# Basic-Computer.net
KiCad netlist of a schematic drawn in EAGLE
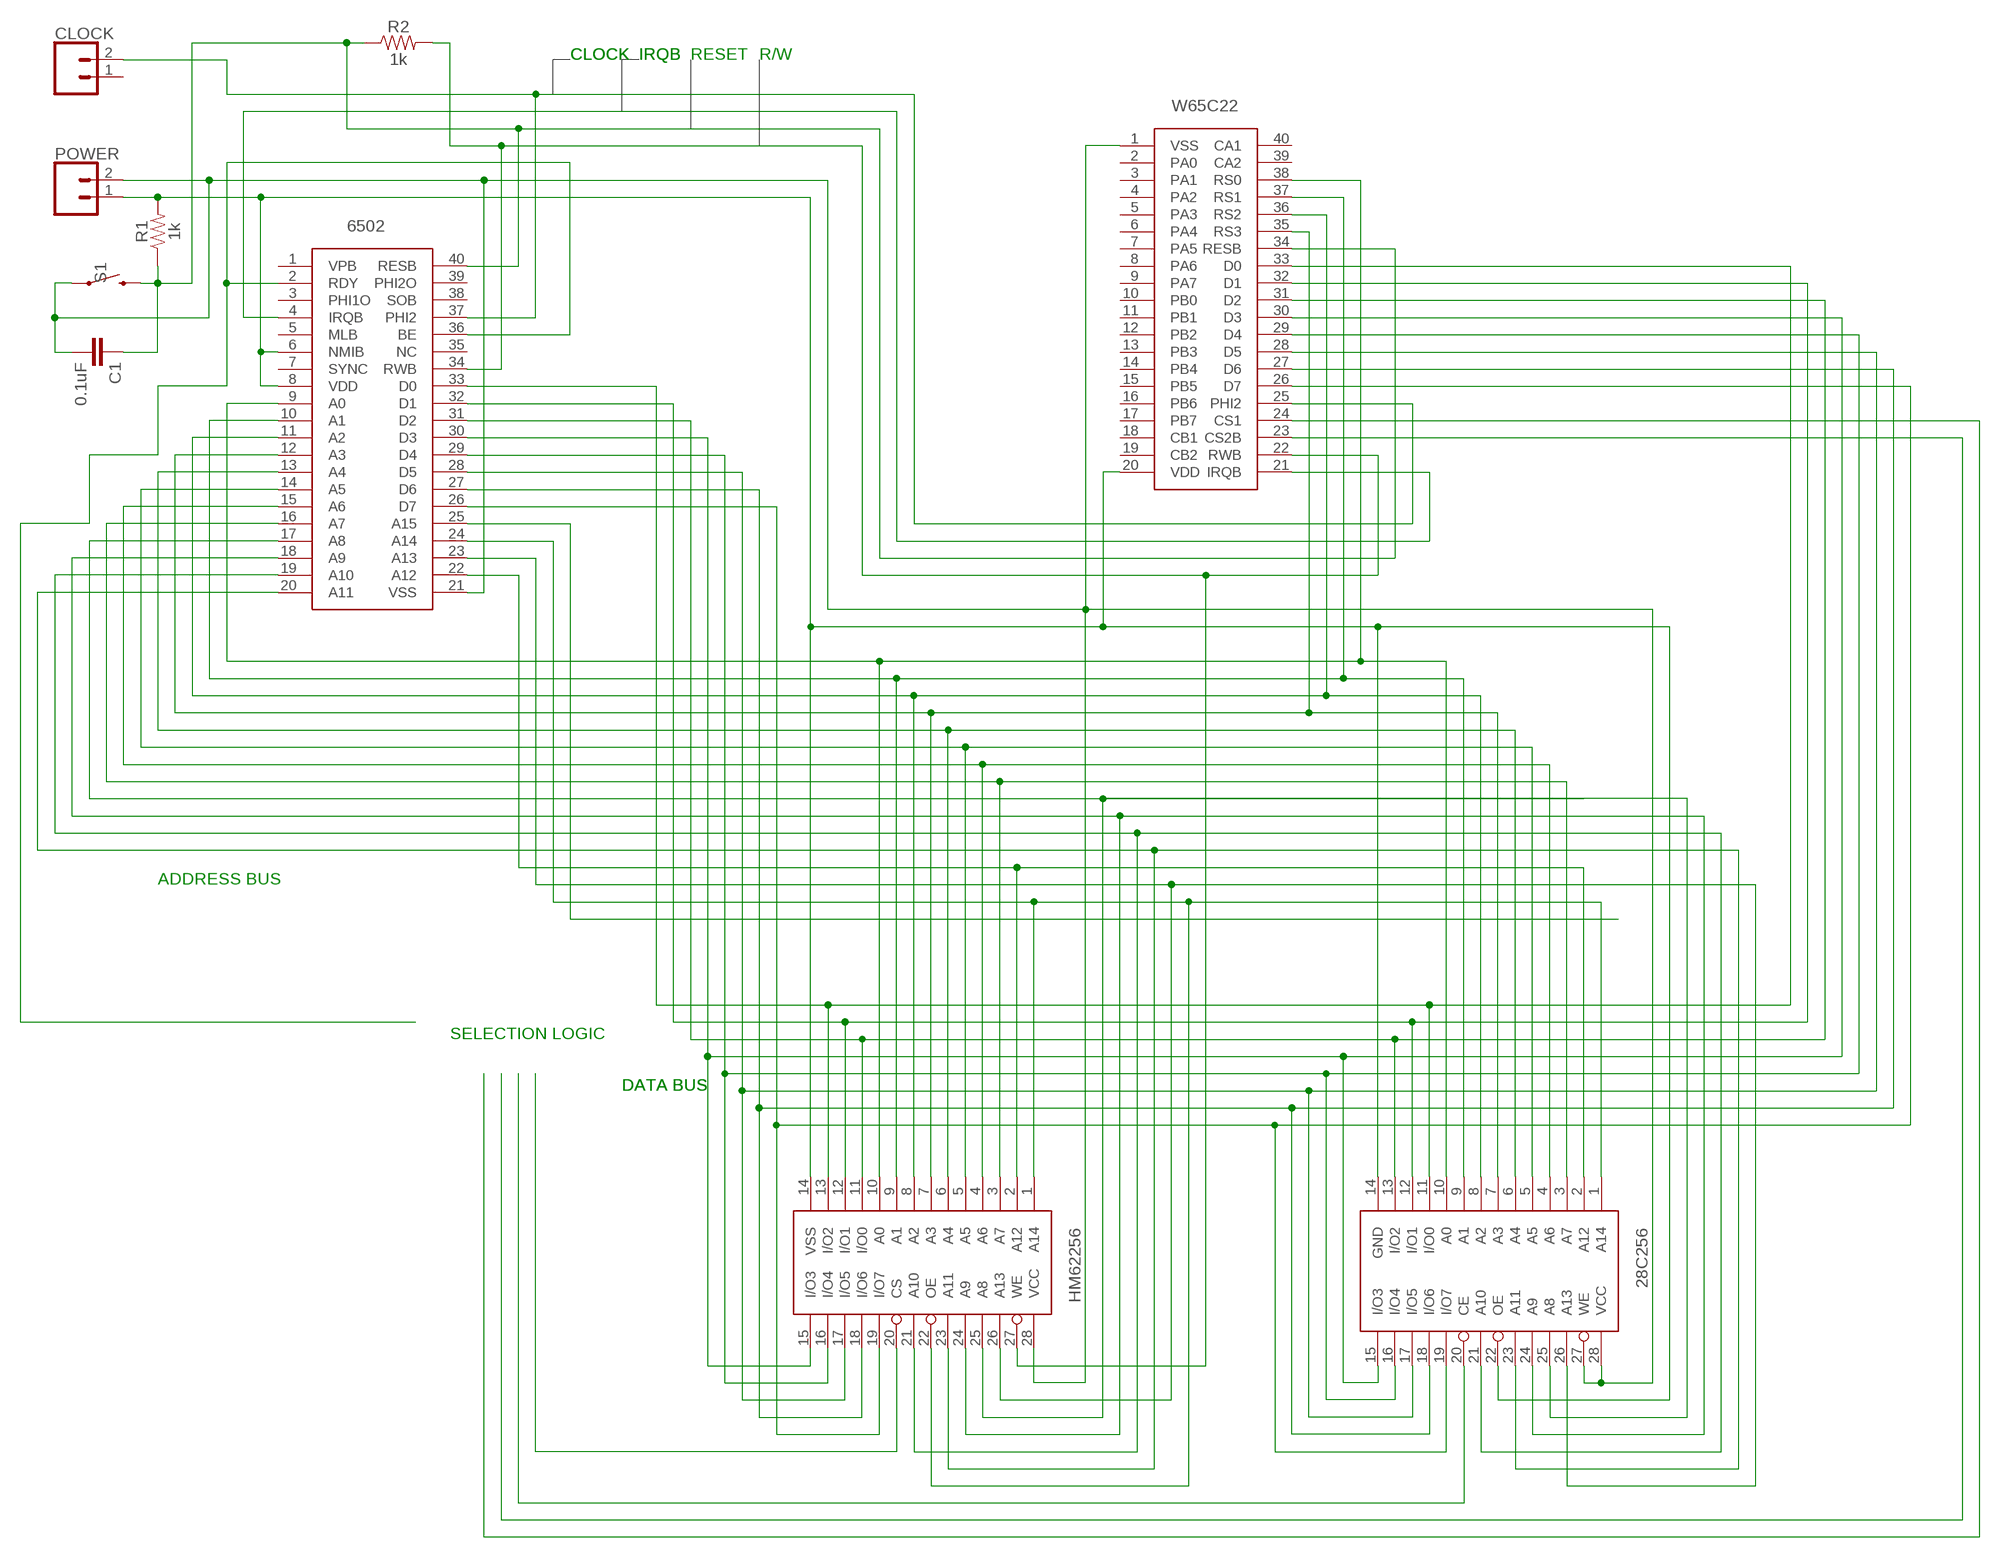
[diagram p0: schematic, sheet 1]

(export (version "E")
  (design (tool "Eeschema 10.0.6"))
  (components
    (comp (ref "C1")
      (value "0.1uF")
      (footprint "eagle-import:0402")
      (libsource (lib "eagle-import") (part "0.1UF-0402-16V-10%"))
    )
    (comp (ref "CLOCK")
      (value "CONN_02POGO_PIN_HOLES_ONLY")
      (footprint "eagle-import:1X02_PP_HOLES_ONLY")
      (libsource (lib "eagle-import") (part "CONN_02POGO_PIN_HOLES_ONLY"))
    )
    (comp (ref "POWER")
      (value "CONN_02POGO_PIN_HOLES_ONLY")
      (footprint "eagle-import:1X02_PP_HOLES_ONLY")
      (libsource (lib "eagle-import") (part "CONN_02POGO_PIN_HOLES_ONLY"))
    )
    (comp (ref "R1")
      (value "1k")
      (footprint "eagle-import:AXIAL-0.3")
      (libsource (lib "eagle-import") (part "1KOHM-HORIZ-1/4W-5%"))
    )
    (comp (ref "R2")
      (value "1k")
      (footprint "eagle-import:AXIAL-0.3")
      (libsource (lib "eagle-import") (part "1KOHM-HORIZ-1/4W-5%"))
    )
    (comp (ref "S1")
      (value "MOMENTARY-SWITCH-SPST-PTH-6.0MM")
      (footprint "eagle-import:TACTILE_SWITCH_PTH_6.0MM")
      (libsource (lib "eagle-import") (part "MOMENTARY-SWITCH-SPST-PTH-6.0MM"))
    )
    (comp (ref "U$1")
      (value "C6502")
      (footprint "eagle-import:DIP1150W53P250L4975H200Q40B")
      (libsource (lib "eagle-import") (part "C6502"))
    )
    (comp (ref "U$2")
      (value "W65C22")
      (footprint "eagle-import:DIP1150W53P250L4975H200Q40B")
      (libsource (lib "eagle-import") (part "W65C22"))
    )
    (comp (ref "U$3")
      (value "28C256")
      (footprint "eagle-import:DIP1722W26P254L3450H508Q28B")
      (libsource (lib "eagle-import") (part "28C256"))
    )
    (comp (ref "U$4")
      (value "HM62256")
      (footprint "eagle-import:DIP1722W26P254L3450H508Q28B")
      (libsource (lib "eagle-import") (part "HM62256"))
    )
  )
  (nets
    (net (code "1") (name "Net-(R1-1)") (class "Default")
      (node (ref "C1") (pin "1") (pinfunction "1_1") (pintype "passive"))
      (node (ref "R1") (pin "P$1") (pinfunction "1_P$1") (pintype "passive"))
      (node (ref "R2") (pin "P$1") (pinfunction "1_P$1") (pintype "passive"))
      (node (ref "S1") (pin "3") (pinfunction "2_3") (pintype "passive"))
      (node (ref "U$1") (pin "40") (pinfunction "RESB_40") (pintype "bidirectional"))
      (node (ref "U$2") (pin "34") (pinfunction "RESB_34") (pintype "bidirectional"))
    )
    (net (code "2") (name "Net-(R1-2)") (class "Default")
      (node (ref "POWER") (pin "1") (pinfunction "1_1") (pintype "passive"))
      (node (ref "R1") (pin "P$2") (pinfunction "2_P$2") (pintype "passive"))
      (node (ref "U$1") (pin "6") (pinfunction "NMIB_6") (pintype "bidirectional"))
      (node (ref "U$1") (pin "8") (pinfunction "VDD_8") (pintype "bidirectional"))
      (node (ref "U$2") (pin "20") (pinfunction "VDD_20") (pintype "bidirectional"))
      (node (ref "U$3") (pin "14") (pinfunction "GND_14") (pintype "bidirectional"))
      (node (ref "U$3") (pin "22") (pinfunction "OE_22") (pintype "bidirectional"))
      (node (ref "U$4") (pin "14") (pinfunction "VSS_14") (pintype "bidirectional"))
    )
    (net (code "3") (name "Net-(R2-2)") (class "Default")
      (node (ref "R2") (pin "P$2") (pinfunction "2_P$2") (pintype "passive"))
      (node (ref "U$1") (pin "34") (pinfunction "RWB_34") (pintype "bidirectional"))
      (node (ref "U$2") (pin "22") (pinfunction "RWB_22") (pintype "bidirectional"))
      (node (ref "U$4") (pin "27") (pinfunction "WE_27") (pintype "bidirectional"))
    )
    (net (code "4") (name "Net-(U$1-A0)") (class "Default")
      (node (ref "U$1") (pin "9") (pinfunction "A0_9") (pintype "bidirectional"))
      (node (ref "U$2") (pin "38") (pinfunction "RS0_38") (pintype "bidirectional"))
      (node (ref "U$3") (pin "10") (pinfunction "A0_10") (pintype "bidirectional"))
      (node (ref "U$4") (pin "10") (pinfunction "A0_10") (pintype "bidirectional"))
    )
    (net (code "5") (name "Net-(U$1-A1)") (class "Default")
      (node (ref "U$1") (pin "10") (pinfunction "A1_10") (pintype "bidirectional"))
      (node (ref "U$2") (pin "37") (pinfunction "RS1_37") (pintype "bidirectional"))
      (node (ref "U$3") (pin "9") (pinfunction "A1_9") (pintype "bidirectional"))
      (node (ref "U$4") (pin "9") (pinfunction "A1_9") (pintype "bidirectional"))
    )
    (net (code "6") (name "Net-(U$1-A2)") (class "Default")
      (node (ref "U$1") (pin "11") (pinfunction "A2_11") (pintype "bidirectional"))
      (node (ref "U$2") (pin "36") (pinfunction "RS2_36") (pintype "bidirectional"))
      (node (ref "U$3") (pin "8") (pinfunction "A2_8") (pintype "bidirectional"))
      (node (ref "U$4") (pin "8") (pinfunction "A2_8") (pintype "bidirectional"))
    )
    (net (code "7") (name "Net-(U$1-A3)") (class "Default")
      (node (ref "U$1") (pin "12") (pinfunction "A3_12") (pintype "bidirectional"))
      (node (ref "U$2") (pin "35") (pinfunction "RS3_35") (pintype "bidirectional"))
      (node (ref "U$3") (pin "7") (pinfunction "A3_7") (pintype "bidirectional"))
      (node (ref "U$4") (pin "7") (pinfunction "A3_7") (pintype "bidirectional"))
    )
    (net (code "8") (name "Net-(U$1-A4)") (class "Default")
      (node (ref "U$1") (pin "13") (pinfunction "A4_13") (pintype "bidirectional"))
      (node (ref "U$3") (pin "6") (pinfunction "A4_6") (pintype "bidirectional"))
      (node (ref "U$4") (pin "6") (pinfunction "A4_6") (pintype "bidirectional"))
    )
    (net (code "9") (name "Net-(U$1-A5)") (class "Default")
      (node (ref "U$1") (pin "14") (pinfunction "A5_14") (pintype "bidirectional"))
      (node (ref "U$3") (pin "5") (pinfunction "A5_5") (pintype "bidirectional"))
      (node (ref "U$4") (pin "5") (pinfunction "A5_5") (pintype "bidirectional"))
    )
    (net (code "10") (name "Net-(U$1-A6)") (class "Default")
      (node (ref "U$1") (pin "15") (pinfunction "A6_15") (pintype "bidirectional"))
      (node (ref "U$3") (pin "4") (pinfunction "A6_4") (pintype "bidirectional"))
      (node (ref "U$4") (pin "4") (pinfunction "A6_4") (pintype "bidirectional"))
    )
    (net (code "11") (name "Net-(U$1-A7)") (class "Default")
      (node (ref "U$1") (pin "16") (pinfunction "A7_16") (pintype "bidirectional"))
      (node (ref "U$3") (pin "3") (pinfunction "A7_3") (pintype "bidirectional"))
      (node (ref "U$4") (pin "3") (pinfunction "A7_3") (pintype "bidirectional"))
    )
    (net (code "12") (name "Net-(U$1-A8)") (class "Default")
      (node (ref "U$1") (pin "17") (pinfunction "A8_17") (pintype "bidirectional"))
      (node (ref "U$3") (pin "25") (pinfunction "A8_25") (pintype "bidirectional"))
      (node (ref "U$4") (pin "25") (pinfunction "A8_25") (pintype "bidirectional"))
    )
    (net (code "13") (name "Net-(U$1-A9)") (class "Default")
      (node (ref "U$1") (pin "18") (pinfunction "A9_18") (pintype "bidirectional"))
      (node (ref "U$3") (pin "24") (pinfunction "A9_24") (pintype "bidirectional"))
      (node (ref "U$4") (pin "24") (pinfunction "A9_24") (pintype "bidirectional"))
    )
    (net (code "14") (name "Net-(U$1-A10)") (class "Default")
      (node (ref "U$1") (pin "19") (pinfunction "A10_19") (pintype "bidirectional"))
      (node (ref "U$3") (pin "21") (pinfunction "A10_21") (pintype "bidirectional"))
      (node (ref "U$4") (pin "21") (pinfunction "A10_21") (pintype "bidirectional"))
    )
    (net (code "15") (name "Net-(U$1-A11)") (class "Default")
      (node (ref "U$1") (pin "20") (pinfunction "A11_20") (pintype "bidirectional"))
      (node (ref "U$3") (pin "23") (pinfunction "A11_23") (pintype "bidirectional"))
      (node (ref "U$4") (pin "23") (pinfunction "A11_23") (pintype "bidirectional"))
    )
    (net (code "16") (name "Net-(U$1-A12)") (class "Default")
      (node (ref "U$1") (pin "22") (pinfunction "A12_22") (pintype "bidirectional"))
      (node (ref "U$3") (pin "2") (pinfunction "A12_2") (pintype "bidirectional"))
      (node (ref "U$4") (pin "2") (pinfunction "A12_2") (pintype "bidirectional"))
    )
    (net (code "17") (name "Net-(U$1-A13)") (class "Default")
      (node (ref "U$1") (pin "23") (pinfunction "A13_23") (pintype "bidirectional"))
      (node (ref "U$3") (pin "26") (pinfunction "A13_26") (pintype "bidirectional"))
      (node (ref "U$4") (pin "26") (pinfunction "A13_26") (pintype "bidirectional"))
    )
    (net (code "18") (name "Net-(U$1-A14)") (class "Default")
      (node (ref "U$1") (pin "24") (pinfunction "A14_24") (pintype "bidirectional"))
      (node (ref "U$3") (pin "1") (pinfunction "A14_1") (pintype "bidirectional"))
      (node (ref "U$4") (pin "1") (pinfunction "A14_1") (pintype "bidirectional"))
      (node (ref "U$4") (pin "22") (pinfunction "OE_22") (pintype "bidirectional"))
    )
    (net (code "19") (name "Net-(U$1-BE)") (class "Default")
      (node (ref "U$1") (pin "2") (pinfunction "RDY_2") (pintype "bidirectional"))
      (node (ref "U$1") (pin "36") (pinfunction "BE_36") (pintype "bidirectional"))
    )
    (net (code "20") (name "Net-(U$1-D0)") (class "Default")
      (node (ref "U$1") (pin "33") (pinfunction "D0_33") (pintype "bidirectional"))
      (node (ref "U$2") (pin "33") (pinfunction "D0_33") (pintype "bidirectional"))
      (node (ref "U$3") (pin "11") (pinfunction "I/O0_11") (pintype "bidirectional"))
      (node (ref "U$4") (pin "13") (pinfunction "I/O2_13") (pintype "bidirectional"))
    )
    (net (code "21") (name "Net-(U$1-D1)") (class "Default")
      (node (ref "U$1") (pin "32") (pinfunction "D1_32") (pintype "bidirectional"))
      (node (ref "U$2") (pin "32") (pinfunction "D1_32") (pintype "bidirectional"))
      (node (ref "U$3") (pin "12") (pinfunction "I/O1_12") (pintype "bidirectional"))
      (node (ref "U$4") (pin "12") (pinfunction "I/O1_12") (pintype "bidirectional"))
    )
    (net (code "22") (name "Net-(U$1-D2)") (class "Default")
      (node (ref "U$1") (pin "31") (pinfunction "D2_31") (pintype "bidirectional"))
      (node (ref "U$2") (pin "31") (pinfunction "D2_31") (pintype "bidirectional"))
      (node (ref "U$3") (pin "13") (pinfunction "I/O2_13") (pintype "bidirectional"))
      (node (ref "U$4") (pin "11") (pinfunction "I/O0_11") (pintype "bidirectional"))
    )
    (net (code "23") (name "Net-(U$1-D3)") (class "Default")
      (node (ref "U$1") (pin "30") (pinfunction "D3_30") (pintype "bidirectional"))
      (node (ref "U$2") (pin "30") (pinfunction "D3_30") (pintype "bidirectional"))
      (node (ref "U$3") (pin "15") (pinfunction "I/O3_15") (pintype "bidirectional"))
      (node (ref "U$4") (pin "15") (pinfunction "I/O3_15") (pintype "bidirectional"))
    )
    (net (code "24") (name "Net-(U$1-D4)") (class "Default")
      (node (ref "U$1") (pin "29") (pinfunction "D4_29") (pintype "bidirectional"))
      (node (ref "U$2") (pin "29") (pinfunction "D4_29") (pintype "bidirectional"))
      (node (ref "U$3") (pin "16") (pinfunction "I/O4_16") (pintype "bidirectional"))
      (node (ref "U$4") (pin "16") (pinfunction "I/O4_16") (pintype "bidirectional"))
    )
    (net (code "25") (name "Net-(U$1-D5)") (class "Default")
      (node (ref "U$1") (pin "28") (pinfunction "D5_28") (pintype "bidirectional"))
      (node (ref "U$2") (pin "28") (pinfunction "D5_28") (pintype "bidirectional"))
      (node (ref "U$3") (pin "17") (pinfunction "I/O5_17") (pintype "bidirectional"))
      (node (ref "U$4") (pin "17") (pinfunction "I/O5_17") (pintype "bidirectional"))
    )
    (net (code "26") (name "Net-(U$1-D6)") (class "Default")
      (node (ref "U$1") (pin "27") (pinfunction "D6_27") (pintype "bidirectional"))
      (node (ref "U$2") (pin "27") (pinfunction "D6_27") (pintype "bidirectional"))
      (node (ref "U$3") (pin "18") (pinfunction "I/O6_18") (pintype "bidirectional"))
      (node (ref "U$4") (pin "18") (pinfunction "I/O6_18") (pintype "bidirectional"))
    )
    (net (code "27") (name "Net-(U$1-D7)") (class "Default")
      (node (ref "U$1") (pin "26") (pinfunction "D7_26") (pintype "bidirectional"))
      (node (ref "U$2") (pin "26") (pinfunction "D7_26") (pintype "bidirectional"))
      (node (ref "U$3") (pin "19") (pinfunction "I/O7_19") (pintype "bidirectional"))
      (node (ref "U$4") (pin "19") (pinfunction "I/O7_19") (pintype "bidirectional"))
    )
    (net (code "28") (name "Net-(U$1-IRQB)") (class "Default")
      (node (ref "U$1") (pin "4") (pinfunction "IRQB_4") (pintype "bidirectional"))
      (node (ref "U$2") (pin "21") (pinfunction "IRQB_21") (pintype "bidirectional"))
    )
    (net (code "29") (name "Net-(U$1-PHI2)") (class "Default")
      (node (ref "CLOCK") (pin "2") (pinfunction "2_2") (pintype "passive"))
      (node (ref "U$1") (pin "37") (pinfunction "PHI2_37") (pintype "bidirectional"))
      (node (ref "U$2") (pin "25") (pinfunction "PHI2_25") (pintype "bidirectional"))
    )
    (net (code "30") (name "Net-(U$1-VSS)") (class "Default")
      (node (ref "C1") (pin "2") (pinfunction "2_2") (pintype "passive"))
      (node (ref "POWER") (pin "2") (pinfunction "2_2") (pintype "passive"))
      (node (ref "S1") (pin "1") (pinfunction "1_1") (pintype "passive"))
      (node (ref "U$1") (pin "21") (pinfunction "VSS_21") (pintype "bidirectional"))
      (node (ref "U$2") (pin "1") (pinfunction "VSS_1") (pintype "bidirectional"))
      (node (ref "U$3") (pin "27") (pinfunction "WE_27") (pintype "bidirectional"))
      (node (ref "U$3") (pin "28") (pinfunction "VCC_28") (pintype "bidirectional"))
      (node (ref "U$4") (pin "28") (pinfunction "VCC_28") (pintype "bidirectional"))
    )
    (net (code "31") (name "unconnected-(CLOCK-Pad1)") (class "Default")
      (node (ref "CLOCK") (pin "1") (pinfunction "1_1") (pintype "passive"))
    )
    (net (code "32") (name "unconnected-(U$1-A15-Pad25)") (class "Default")
      (node (ref "U$1") (pin "25") (pinfunction "A15_25") (pintype "bidirectional"))
    )
    (net (code "33") (name "unconnected-(U$1-MLB-Pad5)") (class "Default")
      (node (ref "U$1") (pin "5") (pinfunction "MLB_5") (pintype "bidirectional"))
    )
    (net (code "34") (name "unconnected-(U$1-NC-Pad35)") (class "Default")
      (node (ref "U$1") (pin "35") (pinfunction "NC_35") (pintype "bidirectional"))
    )
    (net (code "35") (name "unconnected-(U$1-PHI1O-Pad3)") (class "Default")
      (node (ref "U$1") (pin "3") (pinfunction "PHI1O_3") (pintype "bidirectional"))
    )
    (net (code "36") (name "unconnected-(U$1-PHI2O-Pad39)") (class "Default")
      (node (ref "U$1") (pin "39") (pinfunction "PHI2O_39") (pintype "bidirectional"))
    )
    (net (code "37") (name "unconnected-(U$1-SOB-Pad38)") (class "Default")
      (node (ref "U$1") (pin "38") (pinfunction "SOB_38") (pintype "bidirectional"))
    )
    (net (code "38") (name "unconnected-(U$1-SYNC-Pad7)") (class "Default")
      (node (ref "U$1") (pin "7") (pinfunction "SYNC_7") (pintype "bidirectional"))
    )
    (net (code "39") (name "unconnected-(U$1-VPB-Pad1)") (class "Default")
      (node (ref "U$1") (pin "1") (pinfunction "VPB_1") (pintype "bidirectional"))
    )
    (net (code "40") (name "unconnected-(U$2-CA1-Pad40)") (class "Default")
      (node (ref "U$2") (pin "40") (pinfunction "CA1_40") (pintype "bidirectional"))
    )
    (net (code "41") (name "unconnected-(U$2-CA2-Pad39)") (class "Default")
      (node (ref "U$2") (pin "39") (pinfunction "CA2_39") (pintype "bidirectional"))
    )
    (net (code "42") (name "unconnected-(U$2-CB1-Pad18)") (class "Default")
      (node (ref "U$2") (pin "18") (pinfunction "CB1_18") (pintype "bidirectional"))
    )
    (net (code "43") (name "unconnected-(U$2-CB2-Pad19)") (class "Default")
      (node (ref "U$2") (pin "19") (pinfunction "CB2_19") (pintype "bidirectional"))
    )
    (net (code "44") (name "unconnected-(U$2-CS1-Pad24)") (class "Default")
      (node (ref "U$2") (pin "24") (pinfunction "CS1_24") (pintype "bidirectional"))
    )
    (net (code "45") (name "unconnected-(U$2-CS2B-Pad23)") (class "Default")
      (node (ref "U$2") (pin "23") (pinfunction "CS2B_23") (pintype "bidirectional"))
    )
    (net (code "46") (name "unconnected-(U$2-PA0-Pad2)") (class "Default")
      (node (ref "U$2") (pin "2") (pinfunction "PA0_2") (pintype "bidirectional"))
    )
    (net (code "47") (name "unconnected-(U$2-PA1-Pad3)") (class "Default")
      (node (ref "U$2") (pin "3") (pinfunction "PA1_3") (pintype "bidirectional"))
    )
    (net (code "48") (name "unconnected-(U$2-PA2-Pad4)") (class "Default")
      (node (ref "U$2") (pin "4") (pinfunction "PA2_4") (pintype "bidirectional"))
    )
    (net (code "49") (name "unconnected-(U$2-PA3-Pad5)") (class "Default")
      (node (ref "U$2") (pin "5") (pinfunction "PA3_5") (pintype "bidirectional"))
    )
    (net (code "50") (name "unconnected-(U$2-PA4-Pad6)") (class "Default")
      (node (ref "U$2") (pin "6") (pinfunction "PA4_6") (pintype "bidirectional"))
    )
    (net (code "51") (name "unconnected-(U$2-PA5-Pad7)") (class "Default")
      (node (ref "U$2") (pin "7") (pinfunction "PA5_7") (pintype "bidirectional"))
    )
    (net (code "52") (name "unconnected-(U$2-PA6-Pad8)") (class "Default")
      (node (ref "U$2") (pin "8") (pinfunction "PA6_8") (pintype "bidirectional"))
    )
    (net (code "53") (name "unconnected-(U$2-PA7-Pad9)") (class "Default")
      (node (ref "U$2") (pin "9") (pinfunction "PA7_9") (pintype "bidirectional"))
    )
    (net (code "54") (name "unconnected-(U$2-PB0-Pad10)") (class "Default")
      (node (ref "U$2") (pin "10") (pinfunction "PB0_10") (pintype "bidirectional"))
    )
    (net (code "55") (name "unconnected-(U$2-PB1-Pad11)") (class "Default")
      (node (ref "U$2") (pin "11") (pinfunction "PB1_11") (pintype "bidirectional"))
    )
    (net (code "56") (name "unconnected-(U$2-PB2-Pad12)") (class "Default")
      (node (ref "U$2") (pin "12") (pinfunction "PB2_12") (pintype "bidirectional"))
    )
    (net (code "57") (name "unconnected-(U$2-PB3-Pad13)") (class "Default")
      (node (ref "U$2") (pin "13") (pinfunction "PB3_13") (pintype "bidirectional"))
    )
    (net (code "58") (name "unconnected-(U$2-PB4-Pad14)") (class "Default")
      (node (ref "U$2") (pin "14") (pinfunction "PB4_14") (pintype "bidirectional"))
    )
    (net (code "59") (name "unconnected-(U$2-PB5-Pad15)") (class "Default")
      (node (ref "U$2") (pin "15") (pinfunction "PB5_15") (pintype "bidirectional"))
    )
    (net (code "60") (name "unconnected-(U$2-PB6-Pad16)") (class "Default")
      (node (ref "U$2") (pin "16") (pinfunction "PB6_16") (pintype "bidirectional"))
    )
    (net (code "61") (name "unconnected-(U$2-PB7-Pad17)") (class "Default")
      (node (ref "U$2") (pin "17") (pinfunction "PB7_17") (pintype "bidirectional"))
    )
    (net (code "62") (name "unconnected-(U$3-CE-Pad20)") (class "Default")
      (node (ref "U$3") (pin "20") (pinfunction "CE_20") (pintype "bidirectional"))
    )
    (net (code "63") (name "unconnected-(U$4-CS-Pad20)") (class "Default")
      (node (ref "U$4") (pin "20") (pinfunction "CS_20") (pintype "bidirectional"))
    )
  )
)
